# RFM98PW.net
KiCad netlist of a schematic drawn in EAGLE
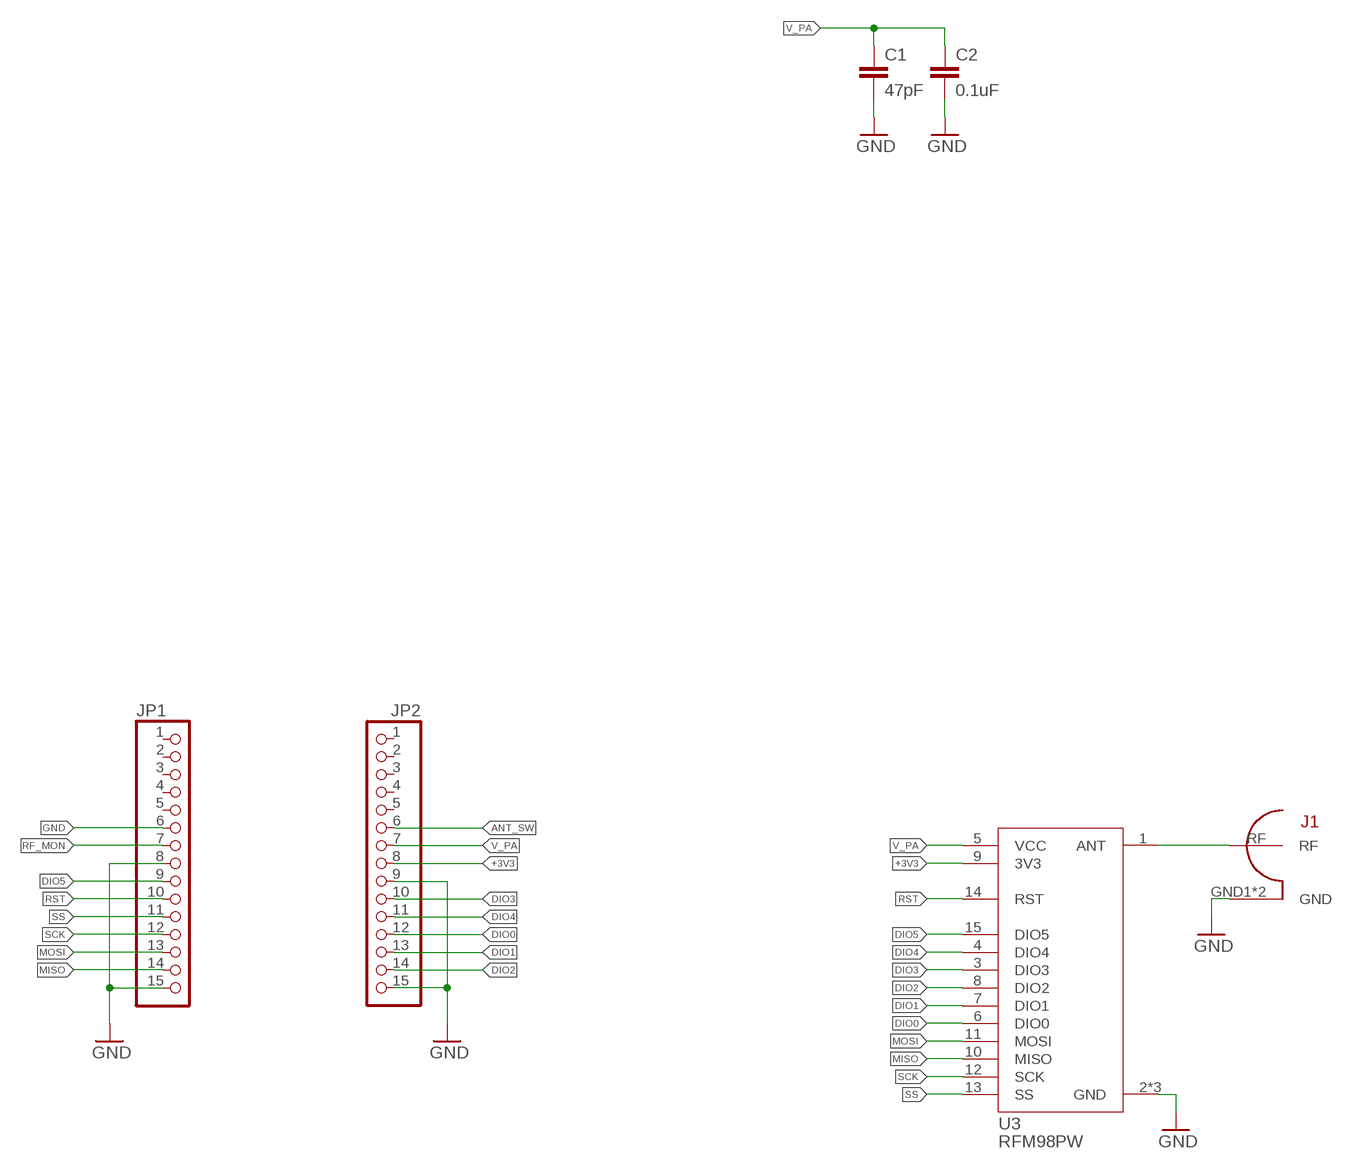
[diagram p0: schematic, sheet 1]

(export (version "E")
  (design (tool "Eeschema 10.0.6"))
  (components
    (comp (ref "C1")
      (value "47pF")
      (footprint "eagle-import:0603")
      (libsource (lib "eagle-import") (part "0603_CAPACITOR"))
    )
    (comp (ref "C2")
      (value "0.1uF")
      (footprint "eagle-import:0603")
      (libsource (lib "eagle-import") (part "0603_CAPACITOR"))
    )
    (comp (ref "J1")
      (value "CON-SMA-EDGE-S")
      (footprint "eagle-import:CON-SMA-EDGE-S")
      (fields (field (name "PARTNO") "CON-SMA-EDGE-S-ND"))
      (libsource (lib "eagle-import") (part "CON-SMA-EDGE-S"))
    )
    (comp (ref "JP1")
      (value "PINHD-1X15")
      (footprint "eagle-import:1X15")
      (libsource (lib "eagle-import") (part "PINHD-1X15"))
    )
    (comp (ref "JP2")
      (value "PINHD-1X15")
      (footprint "eagle-import:1X15")
      (libsource (lib "eagle-import") (part "PINHD-1X15"))
    )
    (comp (ref "U3")
      (value "RFM98PW")
      (footprint "eagle-import:RFM98PW")
      (libsource (lib "eagle-import") (part "RFM98PW"))
    )
  )
  (nets
    (net (code "1") (name "+3V3") (class "Default")
      (node (ref "JP2") (pin "8") (pinfunction "8_8") (pintype "passive"))
      (node (ref "U3") (pin "9") (pinfunction "3V3_9") (pintype "bidirectional"))
    )
    (net (code "2") (name "ANT_SW") (class "Default")
      (node (ref "JP2") (pin "6") (pinfunction "6_6") (pintype "passive"))
    )
    (net (code "3") (name "DIO0") (class "Default")
      (node (ref "JP2") (pin "12") (pinfunction "12_12") (pintype "passive"))
      (node (ref "U3") (pin "6") (pinfunction "DIO0_6") (pintype "bidirectional"))
    )
    (net (code "4") (name "DIO1") (class "Default")
      (node (ref "JP2") (pin "13") (pinfunction "13_13") (pintype "passive"))
      (node (ref "U3") (pin "7") (pinfunction "DIO1_7") (pintype "bidirectional"))
    )
    (net (code "5") (name "DIO2") (class "Default")
      (node (ref "JP2") (pin "14") (pinfunction "14_14") (pintype "passive"))
      (node (ref "U3") (pin "8") (pinfunction "DIO2_8") (pintype "bidirectional"))
    )
    (net (code "6") (name "DIO3") (class "Default")
      (node (ref "JP2") (pin "10") (pinfunction "10_10") (pintype "passive"))
      (node (ref "U3") (pin "3") (pinfunction "DIO3_3") (pintype "bidirectional"))
    )
    (net (code "7") (name "DIO4") (class "Default")
      (node (ref "JP2") (pin "11") (pinfunction "11_11") (pintype "passive"))
      (node (ref "U3") (pin "4") (pinfunction "DIO4_4") (pintype "bidirectional"))
    )
    (net (code "8") (name "DIO5") (class "Default")
      (node (ref "JP1") (pin "9") (pinfunction "9_9") (pintype "passive"))
      (node (ref "U3") (pin "15") (pinfunction "DIO5_15") (pintype "bidirectional"))
    )
    (net (code "9") (name "GND") (class "Default")
      (node (ref "C1") (pin "2") (pinfunction "2_2") (pintype "passive"))
      (node (ref "C2") (pin "2") (pinfunction "2_2") (pintype "passive"))
      (node (ref "J1") (pin "GND1") (pinfunction "GND_GND1") (pintype "bidirectional"))
      (node (ref "J1") (pin "GND2") (pinfunction "GND_GND2") (pintype "bidirectional"))
      (node (ref "JP1") (pin "15") (pinfunction "15_15") (pintype "passive"))
      (node (ref "JP1") (pin "6") (pinfunction "6_6") (pintype "passive"))
      (node (ref "JP1") (pin "8") (pinfunction "8_8") (pintype "passive"))
      (node (ref "JP2") (pin "15") (pinfunction "15_15") (pintype "passive"))
      (node (ref "JP2") (pin "9") (pinfunction "9_9") (pintype "passive"))
      (node (ref "U3") (pin "16") (pinfunction "GND_16") (pintype "bidirectional"))
      (node (ref "U3") (pin "17") (pinfunction "GND_17") (pintype "bidirectional"))
      (node (ref "U3") (pin "2") (pinfunction "GND_2") (pintype "bidirectional"))
    )
    (net (code "10") (name "MISO") (class "Default")
      (node (ref "JP1") (pin "14") (pinfunction "14_14") (pintype "passive"))
      (node (ref "U3") (pin "10") (pinfunction "MISO_10") (pintype "bidirectional"))
    )
    (net (code "11") (name "MOSI") (class "Default")
      (node (ref "JP1") (pin "13") (pinfunction "13_13") (pintype "passive"))
      (node (ref "U3") (pin "11") (pinfunction "MOSI_11") (pintype "bidirectional"))
    )
    (net (code "12") (name "Net-(U3-ANT)") (class "Default")
      (node (ref "J1") (pin "RF") (pinfunction "RF_RF") (pintype "bidirectional"))
      (node (ref "U3") (pin "1") (pinfunction "ANT_1") (pintype "bidirectional"))
    )
    (net (code "13") (name "RF_MON") (class "Default")
      (node (ref "JP1") (pin "7") (pinfunction "7_7") (pintype "passive"))
    )
    (net (code "14") (name "RST") (class "Default")
      (node (ref "JP1") (pin "10") (pinfunction "10_10") (pintype "passive"))
      (node (ref "U3") (pin "14") (pinfunction "RST_14") (pintype "bidirectional"))
    )
    (net (code "15") (name "SCK") (class "Default")
      (node (ref "JP1") (pin "12") (pinfunction "12_12") (pintype "passive"))
      (node (ref "U3") (pin "12") (pinfunction "SCK_12") (pintype "bidirectional"))
    )
    (net (code "16") (name "SS") (class "Default")
      (node (ref "JP1") (pin "11") (pinfunction "11_11") (pintype "passive"))
      (node (ref "U3") (pin "13") (pinfunction "SS_13") (pintype "bidirectional"))
    )
    (net (code "17") (name "V_PA") (class "Default")
      (node (ref "C1") (pin "1") (pinfunction "1_1") (pintype "passive"))
      (node (ref "C2") (pin "1") (pinfunction "1_1") (pintype "passive"))
      (node (ref "JP2") (pin "7") (pinfunction "7_7") (pintype "passive"))
      (node (ref "U3") (pin "5") (pinfunction "VCC_5") (pintype "bidirectional"))
    )
    (net (code "18") (name "unconnected-(JP1-Pad1)") (class "Default")
      (node (ref "JP1") (pin "1") (pinfunction "1_1") (pintype "passive"))
    )
    (net (code "19") (name "unconnected-(JP1-Pad2)") (class "Default")
      (node (ref "JP1") (pin "2") (pinfunction "2_2") (pintype "passive"))
    )
    (net (code "20") (name "unconnected-(JP1-Pad3)") (class "Default")
      (node (ref "JP1") (pin "3") (pinfunction "3_3") (pintype "passive"))
    )
    (net (code "21") (name "unconnected-(JP1-Pad4)") (class "Default")
      (node (ref "JP1") (pin "4") (pinfunction "4_4") (pintype "passive"))
    )
    (net (code "22") (name "unconnected-(JP1-Pad5)") (class "Default")
      (node (ref "JP1") (pin "5") (pinfunction "5_5") (pintype "passive"))
    )
    (net (code "23") (name "unconnected-(JP2-Pad1)") (class "Default")
      (node (ref "JP2") (pin "1") (pinfunction "1_1") (pintype "passive"))
    )
    (net (code "24") (name "unconnected-(JP2-Pad2)") (class "Default")
      (node (ref "JP2") (pin "2") (pinfunction "2_2") (pintype "passive"))
    )
    (net (code "25") (name "unconnected-(JP2-Pad3)") (class "Default")
      (node (ref "JP2") (pin "3") (pinfunction "3_3") (pintype "passive"))
    )
    (net (code "26") (name "unconnected-(JP2-Pad4)") (class "Default")
      (node (ref "JP2") (pin "4") (pinfunction "4_4") (pintype "passive"))
    )
    (net (code "27") (name "unconnected-(JP2-Pad5)") (class "Default")
      (node (ref "JP2") (pin "5") (pinfunction "5_5") (pintype "passive"))
    )
  )
)
